# Power_BZ_LED_HD.net
KiCad netlist of a schematic drawn in Altium Designer
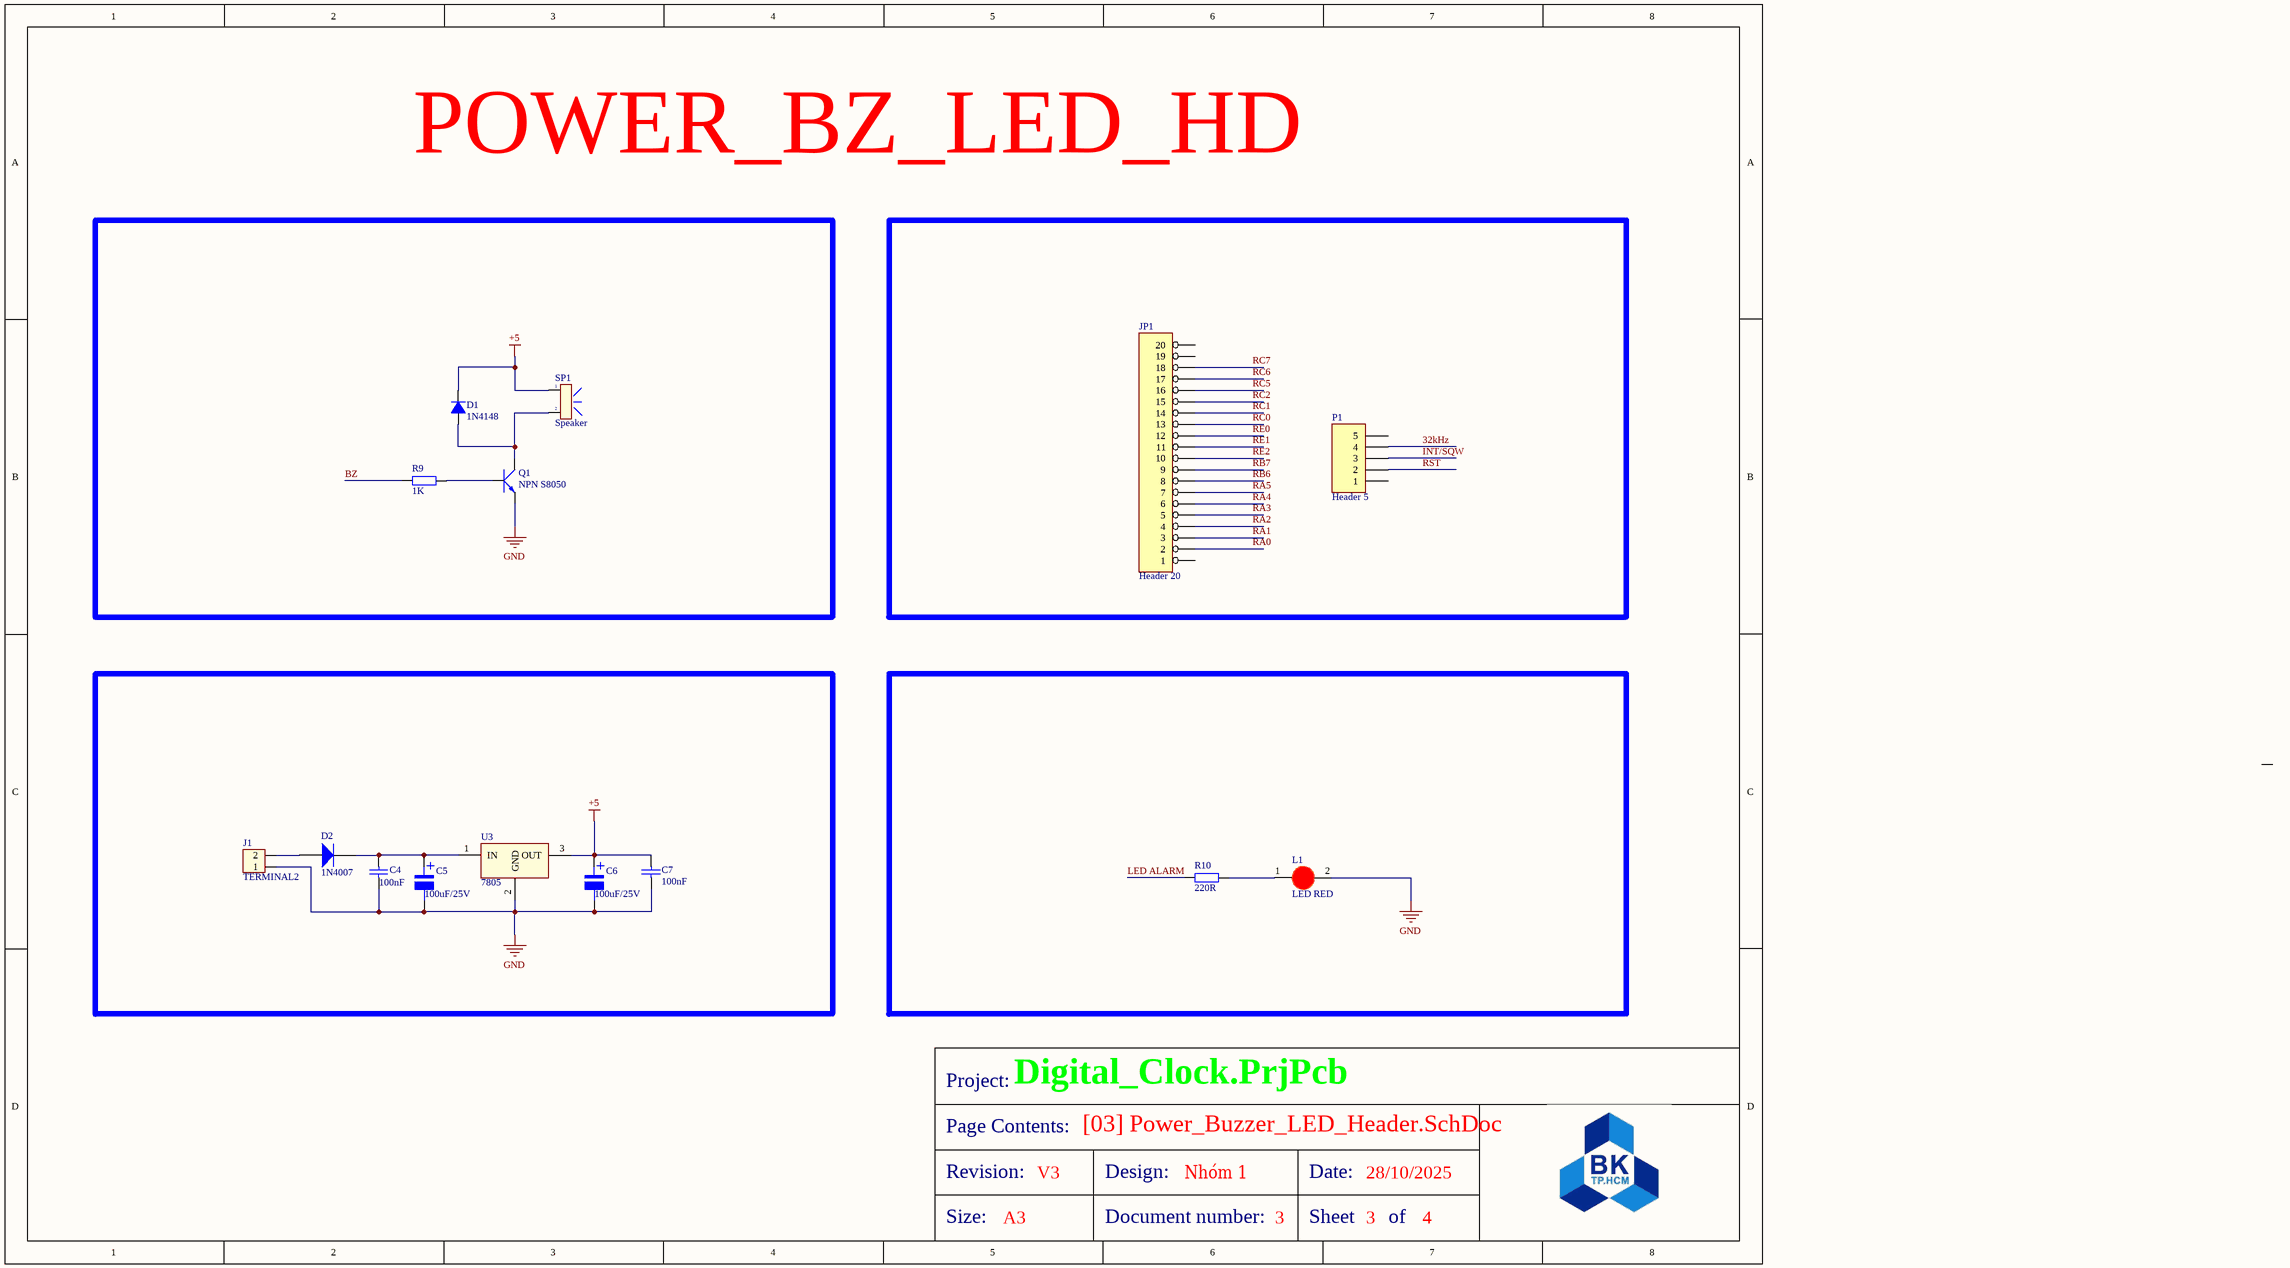
[diagram p0: Power_BZ_LED_HD.SchDoc]

(export (version "E")
  (design (tool "Eeschema 10.0.6"))
  (components
    (comp (ref "C4")
      (value "100nF")
      (footprint "tu gom")
      (description "Cắm")
      (libsource (lib "Capacitor") (part "Tu gom 22pF 50V"))
    )
    (comp (ref "C5")
      (value "100uF/25V")
      (footprint "tu nhom 10 (g)")
      (description "Dán")
      (libsource (lib "Capacitor") (part "Tu Nhom 100uF 35V"))
    )
    (comp (ref "C6")
      (value "100uF/25V")
      (footprint "tu nhom 10 (g)")
      (description "Dán")
      (libsource (lib "Capacitor") (part "Tu Nhom 100uF 35V"))
    )
    (comp (ref "C7")
      (value "100nF")
      (footprint "tu gom")
      (description "Cắm")
      (libsource (lib "Capacitor") (part "Tu gom 22pF 50V"))
    )
    (comp (ref "D1")
      (value "1N4148")
      (footprint "DIODE 0.5A")
      (description "Cắm")
      (libsource (lib "Diode") (part "Diode 1N4148"))
    )
    (comp (ref "D2")
      (value "1N4007")
      (footprint "DIODE SOD-123")
      (description "Dán")
      (libsource (lib "Diode") (part "Diode S4"))
    )
    (comp (ref "J1")
      (value "TERMINAL2")
      (footprint "Header 2P DC 2.54")
      (description "Cắm")
      (libsource (lib "Header") (part "Header 2P 2.54 Duc Cong"))
    )
    (comp (ref "JP1")
      (value "Header 20")
      (description "Header, 20-Pin, Right Angle")
      (libsource (lib "Cty1") (part "Header 20"))
    )
    (comp (ref "L1")
      (value "LED RED")
      (footprint "LED-5MM-RED")
      (description "Cắm")
      (libsource (lib "Led") (part "LED 5mm Do"))
    )
    (comp (ref "P1")
      (value "Header 5")
      (description "Header, 5-Pin")
      (fields (field (name "PUBLISHER") "Altium Limited"))
      (libsource (lib "Cty1") (part "Header 5"))
    )
    (comp (ref "Q1")
      (value "NPN S8050")
      (footprint "QTO-92")
      (description "P 600mW, ECB")
      (libsource (lib "syhaunguyen") (part "NPN_ECB"))
    )
    (comp (ref "R9")
      (value "1K")
      (footprint "tro smd 0603")
      (description "Cắm")
      (libsource (lib "Resistor") (part "Tro Vach 1/4W 5% 4.7k"))
    )
    (comp (ref "R10")
      (value "220R")
      (footprint "tro vach 1/4w")
      (description "Cắm")
      (libsource (lib "Resistor") (part "Tro Vach 1/4W 5% 220R"))
    )
    (comp (ref "SP1")
      (value "Speaker")
      (footprint "SPK")
      (description "Speaker Chip")
      (libsource (lib "syhaunguyen") (part "SPK"))
    )
    (comp (ref "U3")
      (value "7805")
      (footprint "QTO-220")
      (description "On ap +, from + 5 to + 24VDC")
      (libsource (lib "syhaunguyen") (part "LM78xx"))
    )
  )
  (nets
    (net (code "1") (name "+5") (class "Default")
      (node (ref "C6") (pin "1") (pinfunction "1_1") (pintype "passive"))
      (node (ref "C7") (pin "1") (pinfunction "1_1") (pintype "passive"))
      (node (ref "D1") (pin "2") (pinfunction "K_2") (pintype "passive"))
      (node (ref "SP1") (pin "1") (pinfunction "1_1") (pintype "passive"))
      (node (ref "U3") (pin "3") (pinfunction "OUT_3") (pintype "passive"))
    )
    (net (code "2") (name "/32kHz") (class "Default")
      (node (ref "P1") (pin "4") (pinfunction "4_4") (pintype "passive"))
    )
    (net (code "3") (name "/BZ") (class "Default")
      (node (ref "R9") (pin "1") (pinfunction "1_1") (pintype "passive"))
    )
    (net (code "4") (name "/INT{slash}SQW") (class "Default")
      (node (ref "P1") (pin "3") (pinfunction "3_3") (pintype "passive"))
    )
    (net (code "5") (name "/LED ALARM") (class "Default")
      (node (ref "R10") (pin "1") (pinfunction "1_1") (pintype "passive"))
    )
    (net (code "6") (name "/RA0") (class "Default")
      (node (ref "JP1") (pin "2") (pinfunction "2_2") (pintype "passive"))
    )
    (net (code "7") (name "/RA1") (class "Default")
      (node (ref "JP1") (pin "3") (pinfunction "3_3") (pintype "passive"))
    )
    (net (code "8") (name "/RA2") (class "Default")
      (node (ref "JP1") (pin "4") (pinfunction "4_4") (pintype "passive"))
    )
    (net (code "9") (name "/RA3") (class "Default")
      (node (ref "JP1") (pin "5") (pinfunction "5_5") (pintype "passive"))
    )
    (net (code "10") (name "/RA4") (class "Default")
      (node (ref "JP1") (pin "6") (pinfunction "6_6") (pintype "passive"))
    )
    (net (code "11") (name "/RA5") (class "Default")
      (node (ref "JP1") (pin "7") (pinfunction "7_7") (pintype "passive"))
    )
    (net (code "12") (name "/RB6") (class "Default")
      (node (ref "JP1") (pin "8") (pinfunction "8_8") (pintype "passive"))
    )
    (net (code "13") (name "/RB7") (class "Default")
      (node (ref "JP1") (pin "9") (pinfunction "9_9") (pintype "passive"))
    )
    (net (code "14") (name "/RC0") (class "Default")
      (node (ref "JP1") (pin "13") (pinfunction "13_13") (pintype "passive"))
    )
    (net (code "15") (name "/RC1") (class "Default")
      (node (ref "JP1") (pin "14") (pinfunction "14_14") (pintype "passive"))
    )
    (net (code "16") (name "/RC2") (class "Default")
      (node (ref "JP1") (pin "15") (pinfunction "15_15") (pintype "passive"))
    )
    (net (code "17") (name "/RC5") (class "Default")
      (node (ref "JP1") (pin "16") (pinfunction "16_16") (pintype "passive"))
    )
    (net (code "18") (name "/RC6") (class "Default")
      (node (ref "JP1") (pin "17") (pinfunction "17_17") (pintype "passive"))
    )
    (net (code "19") (name "/RC7") (class "Default")
      (node (ref "JP1") (pin "18") (pinfunction "18_18") (pintype "passive"))
    )
    (net (code "20") (name "/RE0") (class "Default")
      (node (ref "JP1") (pin "12") (pinfunction "12_12") (pintype "passive"))
    )
    (net (code "21") (name "/RE1") (class "Default")
      (node (ref "JP1") (pin "11") (pinfunction "11_11") (pintype "passive"))
    )
    (net (code "22") (name "/RE2") (class "Default")
      (node (ref "JP1") (pin "10") (pinfunction "10_10") (pintype "passive"))
    )
    (net (code "23") (name "/RST") (class "Default")
      (node (ref "P1") (pin "2") (pinfunction "2_2") (pintype "passive"))
    )
    (net (code "24") (name "GND") (class "Default")
      (node (ref "C4") (pin "2") (pinfunction "2_2") (pintype "passive"))
      (node (ref "C5") (pin "2") (pinfunction "2_2") (pintype "passive"))
      (node (ref "C6") (pin "2") (pinfunction "2_2") (pintype "passive"))
      (node (ref "C7") (pin "2") (pinfunction "2_2") (pintype "passive"))
      (node (ref "J1") (pin "1") (pinfunction "1_1") (pintype "passive"))
      (node (ref "L1") (pin "2") (pinfunction "K_2") (pintype "passive"))
      (node (ref "Q1") (pin "1") (pinfunction "E_1") (pintype "passive"))
      (node (ref "U3") (pin "2") (pinfunction "GND_2") (pintype "passive"))
    )
    (net (code "25") (name "Net-(D1-A)") (class "Default")
      (node (ref "D1") (pin "1") (pinfunction "A_1") (pintype "passive"))
      (node (ref "Q1") (pin "2") (pinfunction "C_2") (pintype "passive"))
      (node (ref "SP1") (pin "2") (pinfunction "2_2") (pintype "passive"))
    )
    (net (code "26") (name "Net-(D2-A)") (class "Default")
      (node (ref "D2") (pin "1") (pinfunction "A_1") (pintype "passive"))
      (node (ref "J1") (pin "2") (pinfunction "2_2") (pintype "passive"))
    )
    (net (code "27") (name "Net-(D2-K)") (class "Default")
      (node (ref "C4") (pin "1") (pinfunction "1_1") (pintype "passive"))
      (node (ref "C5") (pin "1") (pinfunction "1_1") (pintype "passive"))
      (node (ref "D2") (pin "2") (pinfunction "K_2") (pintype "passive"))
      (node (ref "U3") (pin "1") (pinfunction "IN_1") (pintype "passive"))
    )
    (net (code "28") (name "Net-(L1-A)") (class "Default")
      (node (ref "L1") (pin "1") (pinfunction "A_1") (pintype "passive"))
      (node (ref "R10") (pin "2") (pinfunction "2_2") (pintype "passive"))
    )
    (net (code "29") (name "Net-(Q1-B)") (class "Default")
      (node (ref "Q1") (pin "3") (pinfunction "B_3") (pintype "passive"))
      (node (ref "R9") (pin "2") (pinfunction "2_2") (pintype "passive"))
    )
    (net (code "30") (name "unconnected-(JP1-Pad1)") (class "Default")
      (node (ref "JP1") (pin "1") (pinfunction "1_1") (pintype "passive"))
    )
    (net (code "31") (name "unconnected-(JP1-Pad19)") (class "Default")
      (node (ref "JP1") (pin "19") (pinfunction "19_19") (pintype "passive"))
    )
    (net (code "32") (name "unconnected-(JP1-Pad20)") (class "Default")
      (node (ref "JP1") (pin "20") (pinfunction "20_20") (pintype "passive"))
    )
    (net (code "33") (name "unconnected-(P1-Pad1)") (class "Default")
      (node (ref "P1") (pin "1") (pinfunction "1_1") (pintype "passive"))
    )
    (net (code "34") (name "unconnected-(P1-Pad5)") (class "Default")
      (node (ref "P1") (pin "5") (pinfunction "5_5") (pintype "passive"))
    )
  )
)
